# AutoProgramFTDI.net
KiCad netlist of a schematic drawn in EAGLE
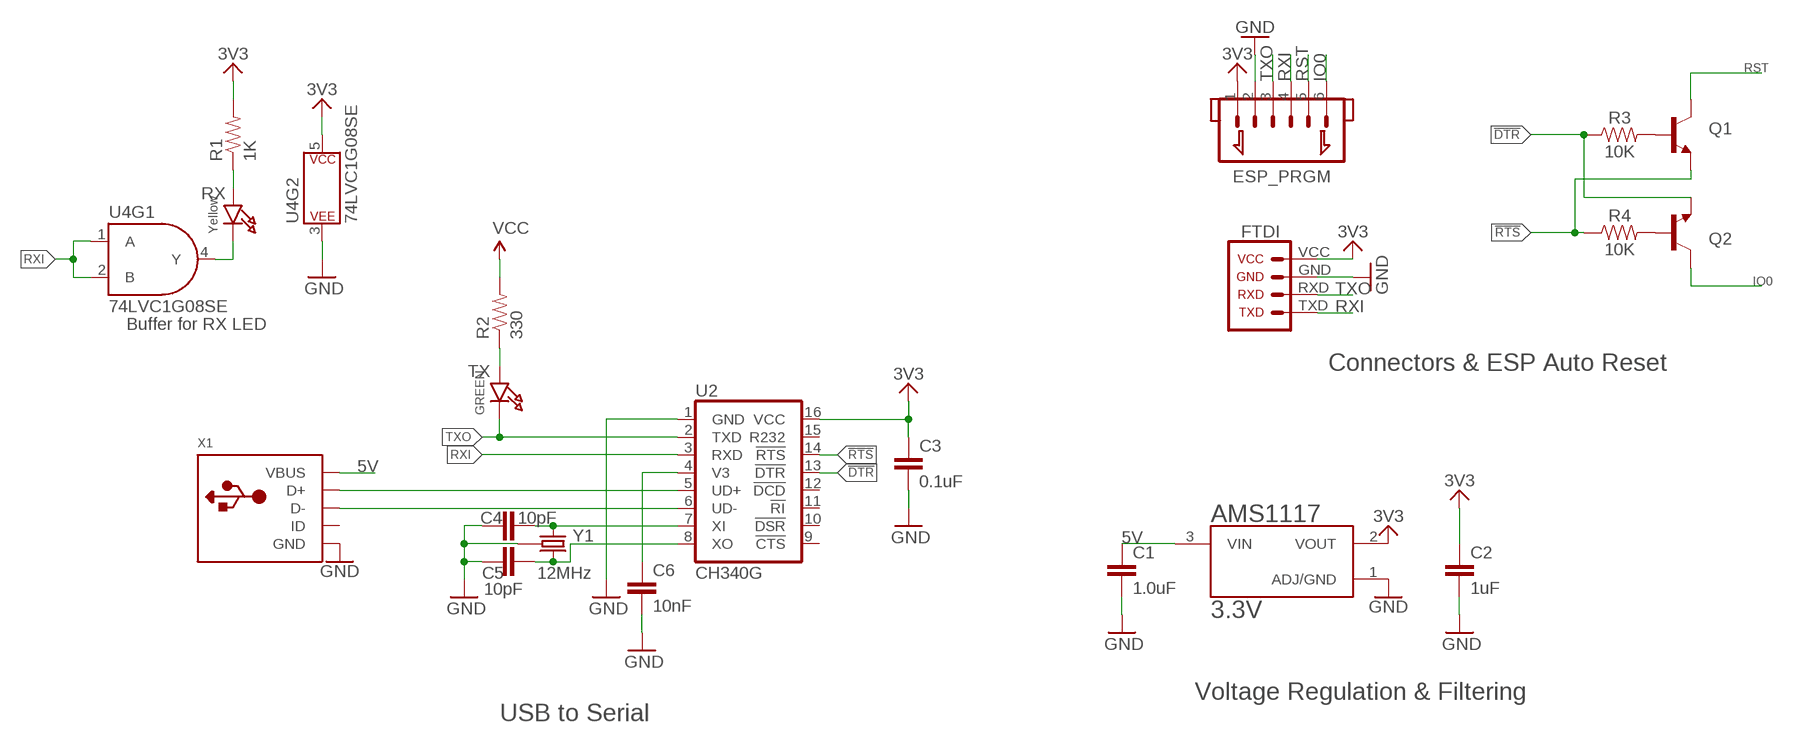
[diagram p0: schematic, sheet 1]

(export (version "E")
  (design (tool "Eeschema 10.0.6"))
  (components
    (comp (ref "AMS1117")
      (value "3.3V")
      (footprint "eagle-import:SOT229P700X180-4N")
      (fields (field (name "MF") "Advanced Monolithic Systems") (field (name "MP") "AMS1117-3.3"))
      (libsource (lib "eagle-import") (part "VREG_AMS1117"))
    )
    (comp (ref "C1")
      (value "1.0uF")
      (footprint "eagle-import:0603-CAP")
      (libsource (lib "eagle-import") (part "1.0UF-16V-10%(0603)"))
    )
    (comp (ref "C2")
      (value "1uF")
      (footprint "eagle-import:0603-CAP")
      (libsource (lib "eagle-import") (part "1.0UF-16V-10%(0603)"))
    )
    (comp (ref "C3")
      (value "0.1uF")
      (footprint "eagle-import:0603-CAP")
      (libsource (lib "eagle-import") (part "0.1UF-25V(+80/-20%)(0603)"))
    )
    (comp (ref "C4")
      (value "10pF")
      (footprint "eagle-import:0603-CAP")
      (libsource (lib "eagle-import") (part "10PF-50V-5%(0603)"))
    )
    (comp (ref "C5")
      (value "10pF")
      (footprint "eagle-import:0603-CAP")
      (libsource (lib "eagle-import") (part "10PF-50V-5%(0603)"))
    )
    (comp (ref "C6")
      (value "10nF")
      (footprint "eagle-import:0603-CAP")
      (libsource (lib "eagle-import") (part "10NF/10000PF-50V-10%(0603)"))
    )
    (comp (ref "ESP_PRGM")
      (value "JST_1.25_6P")
      (footprint "eagle-import:JST1.25_6P")
      (libsource (lib "eagle-import") (part "JST_1.25_6P"))
    )
    (comp (ref "Q1")
      (value "TRANSISTOR_NPNSOT23-3")
      (footprint "eagle-import:SPARKFUN_SOT23-3")
      (libsource (lib "eagle-import") (part "TRANSISTOR_NPNSOT23-3"))
    )
    (comp (ref "Q2")
      (value "TRANSISTOR_NPNSOT23-3")
      (footprint "eagle-import:SPARKFUN_SOT23-3")
      (libsource (lib "eagle-import") (part "TRANSISTOR_NPNSOT23-3"))
    )
    (comp (ref "R1")
      (value "1K")
      (footprint "eagle-import:0603")
      (libsource (lib "eagle-import") (part "RESISTOR0603"))
    )
    (comp (ref "R2")
      (value "330")
      (footprint "eagle-import:0603")
      (libsource (lib "eagle-import") (part "RESISTOR0603"))
    )
    (comp (ref "R3")
      (value "10K")
      (footprint "eagle-import:0603")
      (libsource (lib "eagle-import") (part "RESISTOR0603"))
    )
    (comp (ref "R4")
      (value "10K")
      (footprint "eagle-import:0603")
      (libsource (lib "eagle-import") (part "RESISTOR0603"))
    )
    (comp (ref "RX")
      (value "Yellow")
      (footprint "eagle-import:MICROBUILDER_CHIPLED_0603")
      (libsource (lib "eagle-import") (part "LED0603"))
    )
    (comp (ref "TX")
      (value "GREEN")
      (footprint "eagle-import:MICROBUILDER_CHIPLED_0603")
      (libsource (lib "eagle-import") (part "LED0603"))
    )
    (comp (ref "U$6")
      (value "FTDI")
      (footprint "eagle-import:1X06")
      (libsource (lib "eagle-import") (part "FTDI"))
    )
    (comp (ref "U2")
      (value "CH340G")
      (footprint "eagle-import:SO016")
      (libsource (lib "eagle-import") (part "FTDI_CH340GSMD"))
    )
    (comp (ref "U4")
      (value "74LVC1G08SE")
      (footprint "eagle-import:SOT353")
      (libsource (lib "eagle-import") (part "GATE_7408"))
    )
    (comp (ref "X1")
      (value "USB_MICRO_20329_V2")
      (footprint "eagle-import:MICROUSB_4UCONN_20329_V2")
      (libsource (lib "eagle-import") (part "USB_MICRO_20329_V2"))
    )
    (comp (ref "Y1")
      (value "12MHz")
      (footprint "eagle-import:CRYSTAL-SMD-3.2X2.5")
      (libsource (lib "eagle-import") (part "CRYSTAL-GROUNDED3.2X2.5"))
    )
  )
  (nets
    (net (code "1") (name "/5V") (class "Default")
      (node (ref "AMS1117") (pin "3") (pinfunction "VIN_3") (pintype "input"))
      (node (ref "C1") (pin "1") (pinfunction "1_1") (pintype "passive"))
      (node (ref "X1") (pin "VBUS") (pinfunction "VBUS_VBUS") (pintype "power_in"))
    )
    (net (code "2") (name "/IO0") (class "Default")
      (node (ref "ESP_PRGM") (pin "6") (pinfunction "6_6") (pintype "passive"))
      (node (ref "Q2") (pin "3") (pinfunction "C_3") (pintype "passive"))
    )
    (net (code "3") (name "/RST") (class "Default")
      (node (ref "ESP_PRGM") (pin "5") (pinfunction "5_5") (pintype "passive"))
      (node (ref "Q1") (pin "3") (pinfunction "C_3") (pintype "passive"))
    )
    (net (code "4") (name "/~{DTR}") (class "Default")
      (node (ref "Q2") (pin "2") (pinfunction "E_2") (pintype "passive"))
      (node (ref "R3") (pin "1") (pinfunction "1_1") (pintype "passive"))
      (node (ref "U2") (pin "13") (pinfunction "~{DTR}_13") (pintype "bidirectional"))
    )
    (net (code "5") (name "/~{RTS}") (class "Default")
      (node (ref "Q1") (pin "2") (pinfunction "E_2") (pintype "passive"))
      (node (ref "R4") (pin "1") (pinfunction "1_1") (pintype "passive"))
      (node (ref "U2") (pin "14") (pinfunction "~{RTS}_14") (pintype "bidirectional"))
    )
    (net (code "6") (name "GND") (class "Default")
      (node (ref "AMS1117") (pin "1") (pinfunction "ADJ/GND_1") (pintype "power_in"))
      (node (ref "C1") (pin "2") (pinfunction "2_2") (pintype "passive"))
      (node (ref "C2") (pin "2") (pinfunction "2_2") (pintype "passive"))
      (node (ref "C3") (pin "2") (pinfunction "2_2") (pintype "passive"))
      (node (ref "C4") (pin "1") (pinfunction "1_1") (pintype "passive"))
      (node (ref "C5") (pin "1") (pinfunction "1_1") (pintype "passive"))
      (node (ref "C6") (pin "2") (pinfunction "2_2") (pintype "passive"))
      (node (ref "ESP_PRGM") (pin "2") (pinfunction "2_2") (pintype "passive"))
      (node (ref "U$6") (pin "GND") (pinfunction "GND_GND") (pintype "passive"))
      (node (ref "U2") (pin "1") (pinfunction "GND_1") (pintype "bidirectional"))
      (node (ref "U4") (pin "3") (pinfunction "P$V-_3") (pintype "bidirectional"))
      (node (ref "X1") (pin "BASE@1") (pinfunction "GND_BASE@1") (pintype "power_in"))
      (node (ref "X1") (pin "BASE@2") (pinfunction "GND_BASE@2") (pintype "power_in"))
      (node (ref "X1") (pin "GND") (pinfunction "GND_GND") (pintype "power_in"))
      (node (ref "X1") (pin "SPRT@1") (pinfunction "GND_SPRT@1") (pintype "power_in"))
      (node (ref "X1") (pin "SPRT@2") (pinfunction "GND_SPRT@2") (pintype "power_in"))
      (node (ref "X1") (pin "SPRT@3") (pinfunction "GND_SPRT@3") (pintype "power_in"))
      (node (ref "X1") (pin "SPRT@4") (pinfunction "GND_SPRT@4") (pintype "power_in"))
      (node (ref "Y1") (pin "2") (pinfunction "GND_2") (pintype "passive"))
      (node (ref "Y1") (pin "4") (pinfunction "GND_4") (pintype "passive"))
    )
    (net (code "7") (name "Net-(Q1-B)") (class "Default")
      (node (ref "Q1") (pin "1") (pinfunction "B_1") (pintype "passive"))
      (node (ref "R3") (pin "2") (pinfunction "2_2") (pintype "passive"))
    )
    (net (code "8") (name "Net-(Q2-B)") (class "Default")
      (node (ref "Q2") (pin "1") (pinfunction "B_1") (pintype "passive"))
      (node (ref "R4") (pin "2") (pinfunction "2_2") (pintype "passive"))
    )
    (net (code "9") (name "Net-(R1-Pad1)") (class "Default")
      (node (ref "R1") (pin "1") (pinfunction "1_1") (pintype "passive"))
      (node (ref "RX") (pin "A") (pinfunction "A_A") (pintype "passive"))
    )
    (net (code "10") (name "Net-(R2-Pad1)") (class "Default")
      (node (ref "R2") (pin "1") (pinfunction "1_1") (pintype "passive"))
      (node (ref "TX") (pin "A") (pinfunction "A_A") (pintype "passive"))
    )
    (net (code "11") (name "Net-(U2-UD+)") (class "Default")
      (node (ref "U2") (pin "5") (pinfunction "UD+_5") (pintype "bidirectional"))
      (node (ref "X1") (pin "D+") (pinfunction "D+_D+") (pintype "bidirectional"))
    )
    (net (code "12") (name "Net-(U2-UD-)") (class "Default")
      (node (ref "U2") (pin "6") (pinfunction "UD-_6") (pintype "bidirectional"))
      (node (ref "X1") (pin "D-") (pinfunction "D-_D-") (pintype "bidirectional"))
    )
    (net (code "13") (name "Net-(U2-V3)") (class "Default")
      (node (ref "C6") (pin "1") (pinfunction "1_1") (pintype "passive"))
      (node (ref "U2") (pin "4") (pinfunction "V3_4") (pintype "bidirectional"))
    )
    (net (code "14") (name "Net-(U2-XI)") (class "Default")
      (node (ref "C4") (pin "2") (pinfunction "2_2") (pintype "passive"))
      (node (ref "U2") (pin "7") (pinfunction "XI_7") (pintype "bidirectional"))
      (node (ref "Y1") (pin "1") (pinfunction "1_1") (pintype "passive"))
    )
    (net (code "15") (name "Net-(U2-XO)") (class "Default")
      (node (ref "C5") (pin "2") (pinfunction "2_2") (pintype "passive"))
      (node (ref "U2") (pin "8") (pinfunction "XO_8") (pintype "bidirectional"))
      (node (ref "Y1") (pin "3") (pinfunction "2_3") (pintype "passive"))
    )
    (net (code "16") (name "Net-(U4A-Y)") (class "Default")
      (node (ref "RX") (pin "C") (pinfunction "C_C") (pintype "passive"))
      (node (ref "U4") (pin "4") (pinfunction "Y_4") (pintype "bidirectional"))
    )
    (net (code "17") (name "RXI") (class "Default")
      (node (ref "ESP_PRGM") (pin "4") (pinfunction "4_4") (pintype "passive"))
      (node (ref "U$6") (pin "TXD") (pinfunction "TXD_TXD") (pintype "passive"))
      (node (ref "U2") (pin "3") (pinfunction "RXD_3") (pintype "bidirectional"))
      (node (ref "U4") (pin "1") (pinfunction "A_1") (pintype "bidirectional"))
      (node (ref "U4") (pin "2") (pinfunction "B_2") (pintype "bidirectional"))
    )
    (net (code "18") (name "SUPPLY_3.3V") (class "Default")
      (node (ref "AMS1117") (pin "2") (pinfunction "VOUT_2") (pintype "output"))
      (node (ref "C2") (pin "1") (pinfunction "1_1") (pintype "passive"))
      (node (ref "C3") (pin "1") (pinfunction "1_1") (pintype "passive"))
      (node (ref "ESP_PRGM") (pin "1") (pinfunction "1_1") (pintype "passive"))
      (node (ref "R1") (pin "2") (pinfunction "2_2") (pintype "passive"))
      (node (ref "U$6") (pin "VCC") (pinfunction "VCC_VCC") (pintype "passive"))
      (node (ref "U2") (pin "16") (pinfunction "VCC_16") (pintype "bidirectional"))
      (node (ref "U4") (pin "5") (pinfunction "P$V+_5") (pintype "bidirectional"))
    )
    (net (code "19") (name "TXO") (class "Default")
      (node (ref "ESP_PRGM") (pin "3") (pinfunction "3_3") (pintype "passive"))
      (node (ref "TX") (pin "C") (pinfunction "C_C") (pintype "passive"))
      (node (ref "U$6") (pin "RXD") (pinfunction "RXD_RXD") (pintype "passive"))
      (node (ref "U2") (pin "2") (pinfunction "TXD_2") (pintype "bidirectional"))
    )
    (net (code "20") (name "VCC") (class "Default")
      (node (ref "R2") (pin "2") (pinfunction "2_2") (pintype "passive"))
    )
    (net (code "21") (name "unconnected-(U2-R232-Pad15)") (class "Default")
      (node (ref "U2") (pin "15") (pinfunction "R232_15") (pintype "bidirectional"))
    )
    (net (code "22") (name "unconnected-(U2-~{CTS}-Pad9)") (class "Default")
      (node (ref "U2") (pin "9") (pinfunction "~{CTS}_9") (pintype "bidirectional"))
    )
    (net (code "23") (name "unconnected-(U2-~{DCD}-Pad12)") (class "Default")
      (node (ref "U2") (pin "12") (pinfunction "~{DCD}_12") (pintype "bidirectional"))
    )
    (net (code "24") (name "unconnected-(U2-~{DSR}-Pad10)") (class "Default")
      (node (ref "U2") (pin "10") (pinfunction "~{DSR}_10") (pintype "bidirectional"))
    )
    (net (code "25") (name "unconnected-(U2-~{RI}-Pad11)") (class "Default")
      (node (ref "U2") (pin "11") (pinfunction "~{RI}_11") (pintype "bidirectional"))
    )
    (net (code "26") (name "unconnected-(X1-PadID)") (class "Default")
      (node (ref "X1") (pin "ID") (pinfunction "ID_ID") (pintype "bidirectional"))
    )
  )
)
